# FULL_CB_Servo_REV_D.net
KiCad netlist of a schematic drawn in Altium Designer
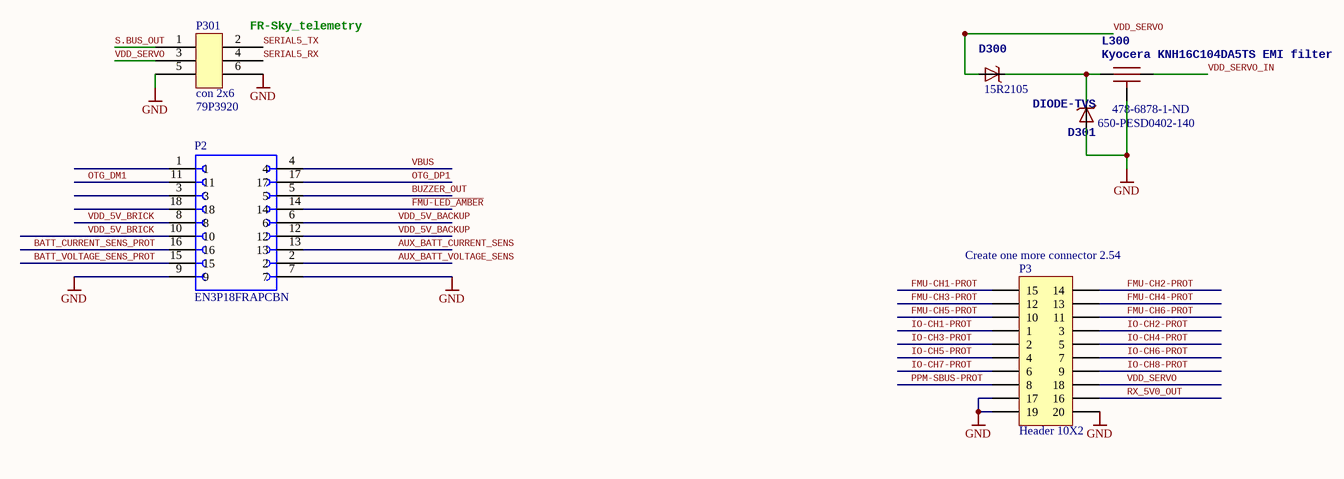
[diagram p0: FULL_CB_Servo_REV_D.SchDoc]

(export (version "E")
  (design (tool "Eeschema 10.0.6"))
  (components
    (comp (ref "D300")
      (value "MSS1P4-M3")
      (footprint "MICROSMP")
      (description "Diode, Schottky, 40V, 1A, MicroSMP, SMD")
      (fields (field (name "SUPPLIER PART NUMBER 1") "15R2105"))
      (libsource (lib "CB_REV_C") (part "DIODE-SCHOTTKY_MSMP"))
    )
    (comp (ref "D301")
      (value "DIODE-TVS")
      (footprint "0402-TVS")
      (description "Diode, TVS, 14VWM, 40VC, 0402, SMD")
      (fields (field (name "SUPPLIER PART NUMBER 1") "650-PESD0402-140"))
      (libsource (lib "CB_REV_C") (part "DIODE-TVS"))
    )
    (comp (ref "L300")
      (value "Kyocera KNH16C104DA5TS EMI filter")
      (footprint "KYOCERA-KNH16-DA")
      (description "Capacitor, Filter, 0.1uF, 25V, 2A, 0603, SMD")
      (fields (field (name "SUPPLIER PART NUMBER 1") "478-6878-1-ND"))
      (libsource (lib "CB_REV_C") (part "KNH16C104DA5TS"))
    )
    (comp (ref "P2")
      (value "EN3P18FRAPCBN")
      (footprint "SWITCHCRAFT_EN3P18FRAPCBN")
      (libsource (lib "CB_REV_C") (part "EN3P18FRAPCBN"))
    )
    (comp (ref "P3")
      (value "Header 10X2")
      (footprint "HDR2X10")
      (description "Header, 10-Pin, Dual row")
      (fields (field (name "PUBLISHER") "Altium Limited"))
      (libsource (lib "Miscellaneous Connectors") (part "Header 10X2"))
    )
    (comp (ref "P301")
      (value "con 2x6")
      (footprint "TSW-103-07-G-D")
      (description "Connector, Header, 6Pos, 2.54MM, Vert, THT, Au")
      (fields (field (name "SUPPLIER PART NUMBER 1") "79P3920"))
      (libsource (lib "CB_REV_D") (part "con 2x6"))
    )
  )
  (nets
    (net (code "1") (name "/AUX_BATT_CURRENT_SENS") (class "Default")
      (node (ref "P2") (pin "13") (pinfunction "13_13") (pintype "passive"))
    )
    (net (code "2") (name "/AUX_BATT_VOLTAGE_SENS") (class "Default")
      (node (ref "P2") (pin "2") (pinfunction "2_2") (pintype "passive"))
    )
    (net (code "3") (name "/BATT_CURRENT_SENS_PROT") (class "Default")
      (node (ref "P2") (pin "16") (pinfunction "16_16") (pintype "passive"))
    )
    (net (code "4") (name "/BATT_VOLTAGE_SENS_PROT") (class "Default")
      (node (ref "P2") (pin "15") (pinfunction "15_15") (pintype "passive"))
    )
    (net (code "5") (name "/BUZZER_OUT") (class "Default")
      (node (ref "P2") (pin "5") (pinfunction "5_5") (pintype "passive"))
    )
    (net (code "6") (name "/FMU-CH1-PROT") (class "Default")
      (node (ref "P3") (pin "15") (pinfunction "15_15") (pintype "passive"))
    )
    (net (code "7") (name "/FMU-CH2-PROT") (class "Default")
      (node (ref "P3") (pin "14") (pinfunction "14_14") (pintype "passive"))
    )
    (net (code "8") (name "/FMU-CH3-PROT") (class "Default")
      (node (ref "P3") (pin "12") (pinfunction "12_12") (pintype "passive"))
    )
    (net (code "9") (name "/FMU-CH4-PROT") (class "Default")
      (node (ref "P3") (pin "13") (pinfunction "13_13") (pintype "passive"))
    )
    (net (code "10") (name "/FMU-CH5-PROT") (class "Default")
      (node (ref "P3") (pin "10") (pinfunction "10_10") (pintype "passive"))
    )
    (net (code "11") (name "/FMU-CH6-PROT") (class "Default")
      (node (ref "P3") (pin "11") (pinfunction "11_11") (pintype "passive"))
    )
    (net (code "12") (name "/IO-CH1-PROT") (class "Default")
      (node (ref "P3") (pin "1") (pinfunction "1_1") (pintype "passive"))
    )
    (net (code "13") (name "/IO-CH2-PROT") (class "Default")
      (node (ref "P3") (pin "3") (pinfunction "3_3") (pintype "passive"))
    )
    (net (code "14") (name "/IO-CH3-PROT") (class "Default")
      (node (ref "P3") (pin "2") (pinfunction "2_2") (pintype "passive"))
    )
    (net (code "15") (name "/IO-CH4-PROT") (class "Default")
      (node (ref "P3") (pin "5") (pinfunction "5_5") (pintype "passive"))
    )
    (net (code "16") (name "/IO-CH5-PROT") (class "Default")
      (node (ref "P3") (pin "4") (pinfunction "4_4") (pintype "passive"))
    )
    (net (code "17") (name "/IO-CH6-PROT") (class "Default")
      (node (ref "P3") (pin "7") (pinfunction "7_7") (pintype "passive"))
    )
    (net (code "18") (name "/IO-CH7-PROT") (class "Default")
      (node (ref "P3") (pin "6") (pinfunction "6_6") (pintype "passive"))
    )
    (net (code "19") (name "/IO-CH8-PROT") (class "Default")
      (node (ref "P3") (pin "9") (pinfunction "9_9") (pintype "passive"))
    )
    (net (code "20") (name "/OTG_DM1") (class "Default")
      (node (ref "P2") (pin "11") (pinfunction "11_11") (pintype "passive"))
    )
    (net (code "21") (name "/OTG_DP1") (class "Default")
      (node (ref "P2") (pin "17") (pinfunction "17_17") (pintype "passive"))
    )
    (net (code "22") (name "/PPM-SBUS-PROT") (class "Default")
      (node (ref "P3") (pin "8") (pinfunction "8_8") (pintype "passive"))
    )
    (net (code "23") (name "/RX_5V0_OUT") (class "Default")
      (node (ref "P3") (pin "16") (pinfunction "16_16") (pintype "passive"))
    )
    (net (code "24") (name "/S.BUS_OUT") (class "Default")
      (node (ref "P301") (pin "1") (pinfunction "1_1") (pintype "passive"))
    )
    (net (code "25") (name "/SERIAL5_RX") (class "Default")
      (node (ref "P301") (pin "4") (pinfunction "4_4") (pintype "passive"))
    )
    (net (code "26") (name "/SERIAL5_TX") (class "Default")
      (node (ref "P301") (pin "2") (pinfunction "2_2") (pintype "passive"))
    )
    (net (code "27") (name "/VBUS") (class "Default")
      (node (ref "P2") (pin "4") (pinfunction "4_4") (pintype "passive"))
    )
    (net (code "28") (name "/VDD_5V_BACKUP") (class "Default")
      (node (ref "P2") (pin "12") (pinfunction "12_12") (pintype "passive"))
      (node (ref "P2") (pin "6") (pinfunction "6_6") (pintype "passive"))
    )
    (net (code "29") (name "/VDD_5V_BRICK") (class "Default")
      (node (ref "P2") (pin "10") (pinfunction "10_10") (pintype "passive"))
      (node (ref "P2") (pin "8") (pinfunction "8_8") (pintype "passive"))
    )
    (net (code "30") (name "/VDD_SERVO") (class "Default")
      (node (ref "D300") (pin "ANODE") (pinfunction "A_ANODE") (pintype "passive"))
      (node (ref "P3") (pin "18") (pinfunction "18_18") (pintype "passive"))
      (node (ref "P301") (pin "3") (pinfunction "3_3") (pintype "passive"))
    )
    (net (code "31") (name "/VDD_SERVO_IN") (class "Default")
      (node (ref "L300") (pin "P$2") (pinfunction "P$2_P$2") (pintype "passive"))
    )
    (net (code "32") (name "/~{FMU-LED_AMBER}") (class "Default")
      (node (ref "P2") (pin "14") (pinfunction "14_14") (pintype "passive"))
    )
    (net (code "33") (name "GND") (class "Default")
      (node (ref "D301") (pin "A") (pinfunction "A_A") (pintype "passive"))
      (node (ref "L300") (pin "GND") (pinfunction "GND_GND") (pintype "passive"))
      (node (ref "P2") (pin "7") (pinfunction "7_7") (pintype "passive"))
      (node (ref "P2") (pin "9") (pinfunction "9_9") (pintype "passive"))
      (node (ref "P3") (pin "17") (pinfunction "17_17") (pintype "passive"))
      (node (ref "P3") (pin "19") (pinfunction "19_19") (pintype "passive"))
      (node (ref "P3") (pin "20") (pinfunction "20_20") (pintype "passive"))
      (node (ref "P301") (pin "5") (pinfunction "5_5") (pintype "passive"))
      (node (ref "P301") (pin "6") (pinfunction "6_6") (pintype "passive"))
    )
    (net (code "34") (name "Net-(D300-C)") (class "Default")
      (node (ref "D300") (pin "CATHODE") (pinfunction "C_CATHODE") (pintype "passive"))
      (node (ref "D301") (pin "C") (pinfunction "C_C") (pintype "passive"))
      (node (ref "L300") (pin "P$1") (pinfunction "P$1_P$1") (pintype "passive"))
    )
    (net (code "35") (name "unconnected-(P2-Pad1)") (class "Default")
      (node (ref "P2") (pin "1") (pinfunction "1_1") (pintype "passive"))
    )
    (net (code "36") (name "unconnected-(P2-Pad3)") (class "Default")
      (node (ref "P2") (pin "3") (pinfunction "3_3") (pintype "passive"))
    )
    (net (code "37") (name "unconnected-(P2-Pad18)") (class "Default")
      (node (ref "P2") (pin "18") (pinfunction "18_18") (pintype "passive"))
    )
  )
)
